# bicyclelab-charger-protection.net
KiCad netlist of a schematic drawn in EAGLE
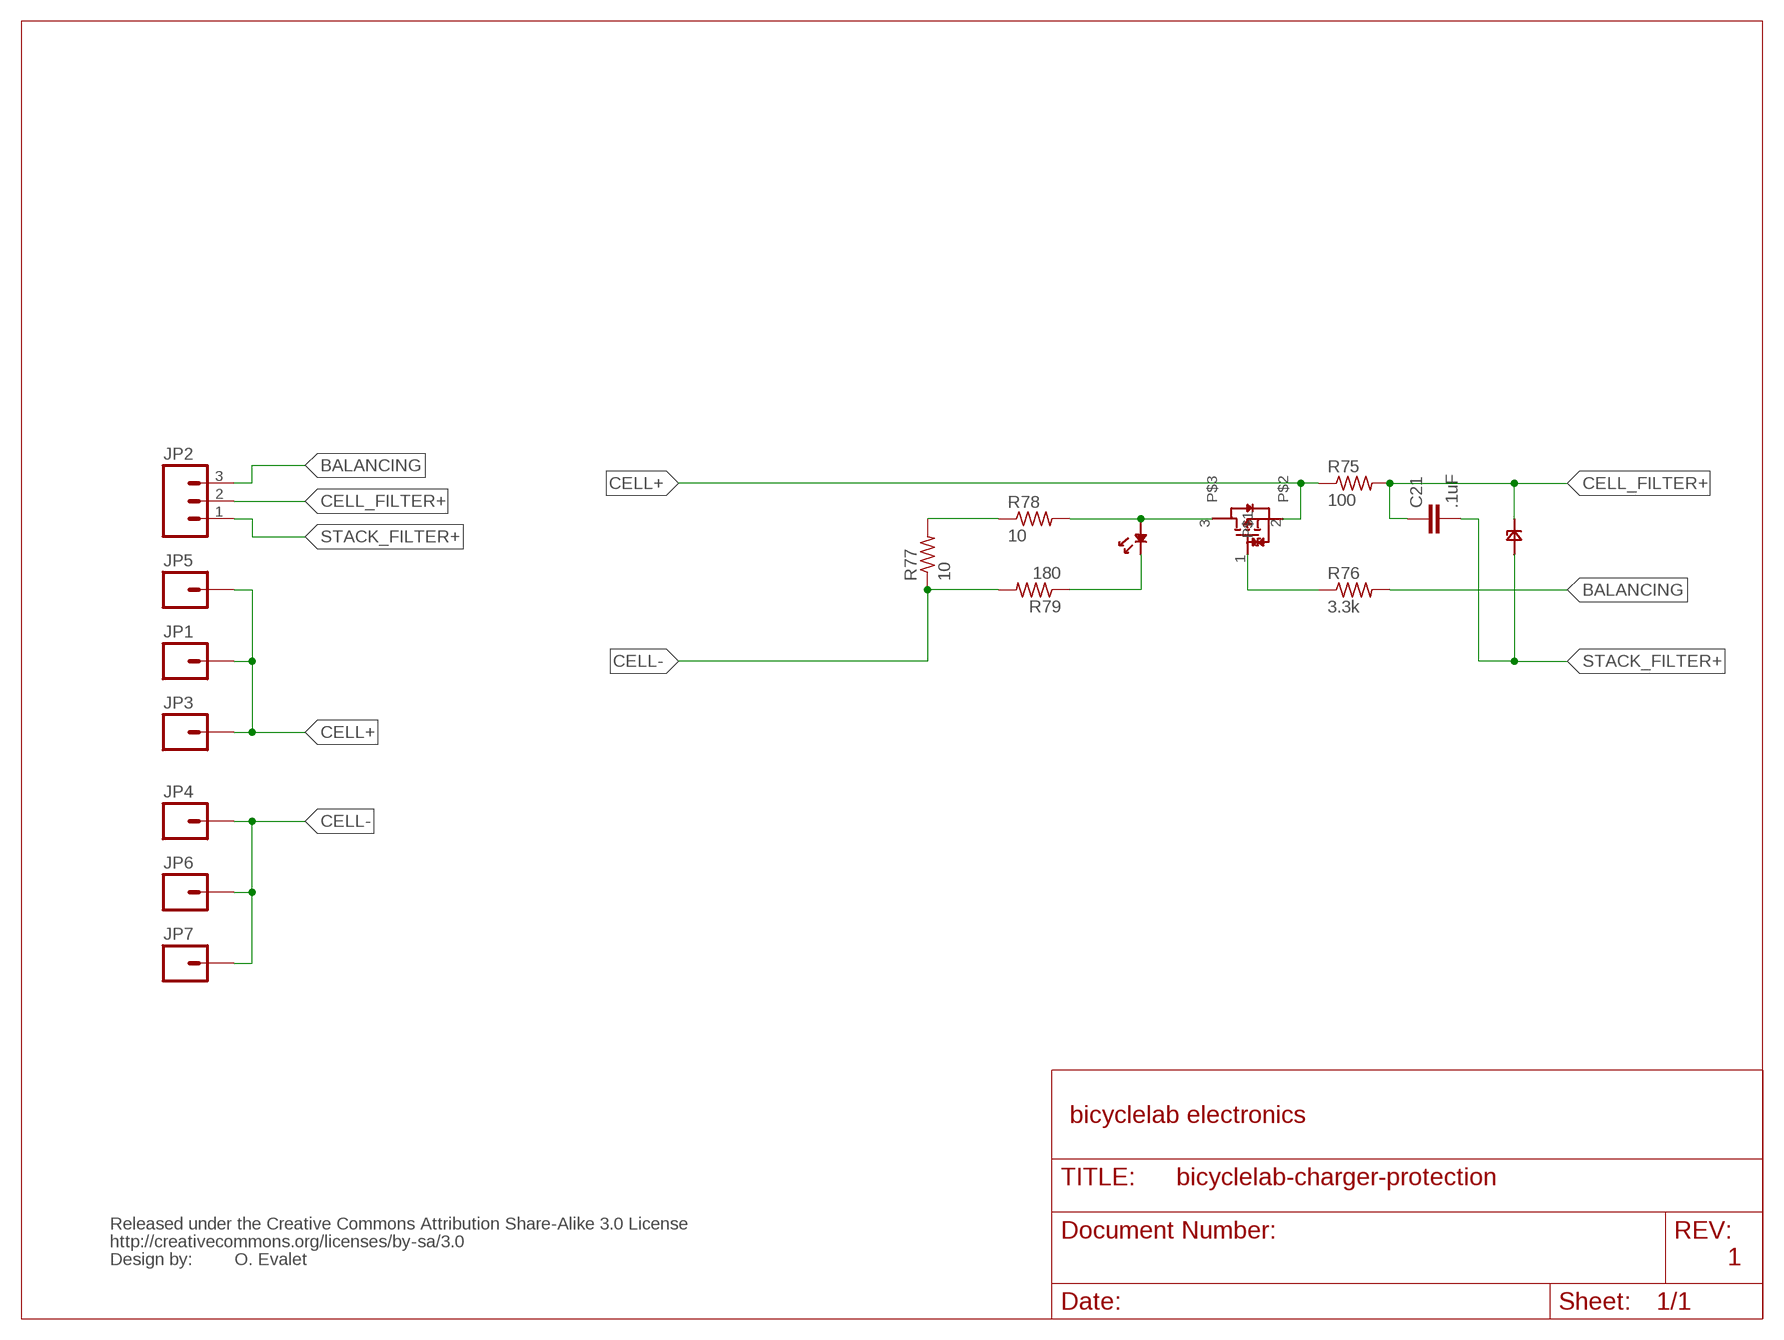
[diagram p0: schematic, sheet 1]

(export (version "E")
  (design (tool "Eeschema 10.0.6"))
  (components
    (comp (ref "C21")
      (value ".1uF")
      (footprint "eagle-import:C0402")
      (libsource (lib "eagle-import") (part "C-EUC0402"))
    )
    (comp (ref "JP1")
      (value "M01SMD-4.5X1.5")
      (footprint "eagle-import:PAD-1.5X4.5")
      (libsource (lib "eagle-import") (part "M01SMD-4.5X1.5"))
    )
    (comp (ref "JP2")
      (value "M03PTH")
      (footprint "eagle-import:1X03")
      (libsource (lib "eagle-import") (part "M03PTH"))
    )
    (comp (ref "JP3")
      (value "M01SMD-4.5X1.5")
      (footprint "eagle-import:PAD-1.5X4.5")
      (libsource (lib "eagle-import") (part "M01SMD-4.5X1.5"))
    )
    (comp (ref "JP4")
      (value "M01SMD-4.5X1.5")
      (footprint "eagle-import:PAD-1.5X4.5")
      (libsource (lib "eagle-import") (part "M01SMD-4.5X1.5"))
    )
    (comp (ref "JP5")
      (value "M01SMD-4.5X1.5")
      (footprint "eagle-import:PAD-1.5X4.5")
      (libsource (lib "eagle-import") (part "M01SMD-4.5X1.5"))
    )
    (comp (ref "JP6")
      (value "M01SMD-4.5X1.5")
      (footprint "eagle-import:PAD-1.5X4.5")
      (libsource (lib "eagle-import") (part "M01SMD-4.5X1.5"))
    )
    (comp (ref "JP7")
      (value "M01SMD-4.5X1.5")
      (footprint "eagle-import:PAD-1.5X4.5")
      (libsource (lib "eagle-import") (part "M01SMD-4.5X1.5"))
    )
    (comp (ref "LED12")
      (value "LED-0805")
      (footprint "eagle-import:0805")
      (libsource (lib "eagle-import") (part "LED-0805"))
    )
    (comp (ref "PD12")
      (value "PDZ7.5B")
      (footprint "eagle-import:SOD323")
      (libsource (lib "eagle-import") (part "PDZ7.5B"))
    )
    (comp (ref "R75")
      (value "100")
      (footprint "eagle-import:R0402")
      (libsource (lib "eagle-import") (part "R-US_R0402"))
    )
    (comp (ref "R76")
      (value "3.3k")
      (footprint "eagle-import:R0402")
      (libsource (lib "eagle-import") (part "R-US_R0402"))
    )
    (comp (ref "R77")
      (value "10")
      (footprint "eagle-import:R2512")
      (libsource (lib "eagle-import") (part "R-US_R2512"))
    )
    (comp (ref "R78")
      (value "10")
      (footprint "eagle-import:R2512")
      (libsource (lib "eagle-import") (part "R-US_R2512"))
    )
    (comp (ref "R79")
      (value "180")
      (footprint "eagle-import:R0805")
      (libsource (lib "eagle-import") (part "R-US_R0805"))
    )
    (comp (ref "T12")
      (value "RTR020P02")
      (footprint "eagle-import:TSMT3")
      (libsource (lib "eagle-import") (part "RTR020P02"))
    )
    (comp (ref "U$5")
      (value "CREATIVE_COMMONS")
      (footprint "eagle-import:CREATIVE_COMMONS")
      (libsource (lib "eagle-import") (part "CREATIVE_COMMONS"))
    )
  )
  (nets
    (net (code "1") (name "BALANCING") (class "Default")
      (node (ref "JP2") (pin "3") (pinfunction "3_3") (pintype "passive"))
      (node (ref "R76") (pin "2") (pinfunction "2_2") (pintype "passive"))
    )
    (net (code "2") (name "CELL+") (class "Default")
      (node (ref "JP1") (pin "P$1") (pinfunction "1_P$1") (pintype "passive"))
      (node (ref "JP3") (pin "P$1") (pinfunction "1_P$1") (pintype "passive"))
      (node (ref "JP5") (pin "P$1") (pinfunction "1_P$1") (pintype "passive"))
      (node (ref "R75") (pin "1") (pinfunction "1_1") (pintype "passive"))
      (node (ref "T12") (pin "2") (pinfunction "P$2_2") (pintype "passive"))
    )
    (net (code "3") (name "CELL-") (class "Default")
      (node (ref "JP4") (pin "P$1") (pinfunction "1_P$1") (pintype "passive"))
      (node (ref "JP6") (pin "P$1") (pinfunction "1_P$1") (pintype "passive"))
      (node (ref "JP7") (pin "P$1") (pinfunction "1_P$1") (pintype "passive"))
      (node (ref "R77") (pin "1") (pinfunction "1_1") (pintype "passive"))
      (node (ref "R79") (pin "2") (pinfunction "2_2") (pintype "passive"))
    )
    (net (code "4") (name "CELL_FILTER+") (class "Default")
      (node (ref "C21") (pin "1") (pinfunction "1_1") (pintype "passive"))
      (node (ref "JP2") (pin "2") (pinfunction "2_2") (pintype "passive"))
      (node (ref "PD12") (pin "P$1") (pinfunction "P$1_P$1") (pintype "passive"))
      (node (ref "R75") (pin "2") (pinfunction "2_2") (pintype "passive"))
    )
    (net (code "5") (name "Net-(LED12-PadP$1)") (class "Default")
      (node (ref "LED12") (pin "P$1") (pinfunction "P$1_P$1") (pintype "passive"))
      (node (ref "R79") (pin "1") (pinfunction "1_1") (pintype "passive"))
    )
    (net (code "6") (name "Net-(R77-Pad2)") (class "Default")
      (node (ref "R77") (pin "2") (pinfunction "2_2") (pintype "passive"))
      (node (ref "R78") (pin "1") (pinfunction "1_1") (pintype "passive"))
    )
    (net (code "7") (name "Net-(T12-P$1)") (class "Default")
      (node (ref "R76") (pin "1") (pinfunction "1_1") (pintype "passive"))
      (node (ref "T12") (pin "1") (pinfunction "P$1_1") (pintype "passive"))
    )
    (net (code "8") (name "Net-(T12-P$3)") (class "Default")
      (node (ref "LED12") (pin "P$2") (pinfunction "P$2_P$2") (pintype "passive"))
      (node (ref "R78") (pin "2") (pinfunction "2_2") (pintype "passive"))
      (node (ref "T12") (pin "3") (pinfunction "P$3_3") (pintype "passive"))
    )
    (net (code "9") (name "STACK_FILTER+") (class "Default")
      (node (ref "C21") (pin "2") (pinfunction "2_2") (pintype "passive"))
      (node (ref "JP2") (pin "1") (pinfunction "1_1") (pintype "passive"))
      (node (ref "PD12") (pin "P$2") (pinfunction "P$2_P$2") (pintype "passive"))
    )
  )
)
